# TALLER1.net
KiCad netlist of a schematic drawn in EAGLE
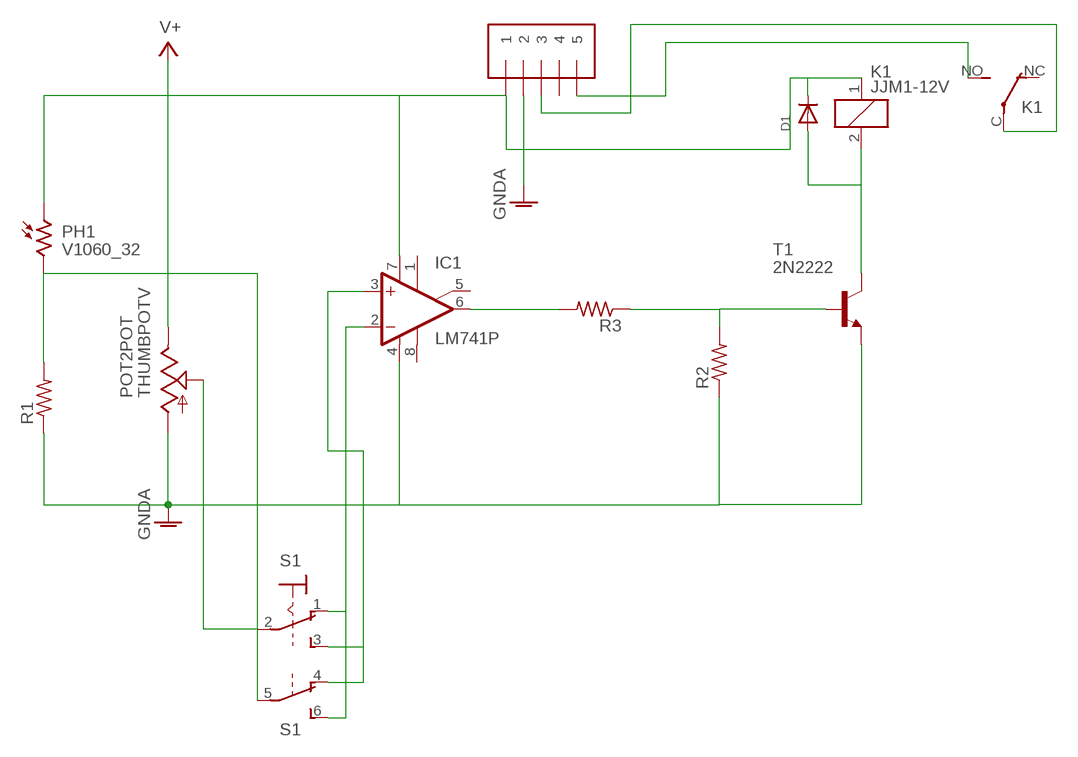
[diagram p0: schematic, sheet 1]

(export (version "E")
  (design (tool "Eeschema 10.0.6"))
  (components
    (comp (ref "D1")
      (value "DIODEDO-1N4148")
      (footprint "eagle-import:DO-1N4148")
      (libsource (lib "eagle-import") (part "DIODEDO-1N4148"))
    )
    (comp (ref "IC1")
      (value "LM741P")
      (footprint "eagle-import:DIL08")
      (libsource (lib "eagle-import") (part "741PLM"))
    )
    (comp (ref "J2")
      (value "1X5")
      (footprint "eagle-import:1X05-3.5MM")
      (libsource (lib "eagle-import") (part "1X5"))
    )
    (comp (ref "K1")
      (value "JJM1-12V")
      (footprint "eagle-import:JJM1C")
      (fields (field (name "MF") "AROMAT/ MATSUSHITA"))
      (libsource (lib "eagle-import") (part "JJM1-12V"))
    )
    (comp (ref "PH1")
      (value "V1060_32")
      (footprint "eagle-import:TO-5_V10")
      (libsource (lib "eagle-import") (part "?1060V_32"))
    )
    (comp (ref "POT2")
      (value "THUMBPOTV")
      (footprint "eagle-import:THUMBWHEELV")
      (libsource (lib "eagle-import") (part "THUMBPOTV"))
    )
    (comp (ref "R1")
      (value "R-US_0207/10")
      (footprint "eagle-import:0207_10")
      (libsource (lib "eagle-import") (part "R-US_0207/10"))
    )
    (comp (ref "R2")
      (value "R-US_0207/10")
      (footprint "eagle-import:0207_10")
      (libsource (lib "eagle-import") (part "R-US_0207/10"))
    )
    (comp (ref "R3")
      (value "R-US_0207/10")
      (footprint "eagle-import:0207_10")
      (libsource (lib "eagle-import") (part "R-US_0207/10"))
    )
    (comp (ref "S1")
      (value "320-938")
      (footprint "eagle-import:320-938")
      (libsource (lib "eagle-import") (part "320-938"))
    )
    (comp (ref "T1")
      (value "2N2222")
      (footprint "eagle-import:TO18")
      (libsource (lib "eagle-import") (part "2N2222"))
    )
  )
  (nets
    (net (code "1") (name "GNDA") (class "Default")
      (node (ref "IC1") (pin "4") (pinfunction "V-_4") (pintype "power_in"))
      (node (ref "J2") (pin "2") (pinfunction "2_2") (pintype "passive"))
      (node (ref "POT2") (pin "A") (pinfunction "A_A") (pintype "passive"))
      (node (ref "R1") (pin "1") (pinfunction "1_1") (pintype "passive"))
      (node (ref "R2") (pin "1") (pinfunction "1_1") (pintype "passive"))
      (node (ref "T1") (pin "1") (pinfunction "E_1") (pintype "passive"))
    )
    (net (code "2") (name "Net-(IC1-+IN)") (class "Default")
      (node (ref "IC1") (pin "3") (pinfunction "+IN_3") (pintype "input"))
      (node (ref "S1") (pin "3") (pinfunction "S_3") (pintype "passive"))
      (node (ref "S1") (pin "4") (pinfunction "O_4") (pintype "passive"))
    )
    (net (code "3") (name "Net-(IC1--IN)") (class "Default")
      (node (ref "IC1") (pin "2") (pinfunction "-IN_2") (pintype "input"))
      (node (ref "S1") (pin "1") (pinfunction "O_1") (pintype "passive"))
      (node (ref "S1") (pin "6") (pinfunction "S_6") (pintype "passive"))
    )
    (net (code "4") (name "Net-(IC1-OUT)") (class "Default")
      (node (ref "IC1") (pin "6") (pinfunction "OUT_6") (pintype "output"))
      (node (ref "R3") (pin "2") (pinfunction "2_2") (pintype "passive"))
    )
    (net (code "5") (name "Net-(K1B-P)") (class "Default")
      (node (ref "J2") (pin "3") (pinfunction "3_3") (pintype "passive"))
      (node (ref "K1") (pin "C") (pinfunction "P_C") (pintype "passive"))
    )
    (net (code "6") (name "Net-(K1B-S)") (class "Default")
      (node (ref "J2") (pin "5") (pinfunction "5_5") (pintype "passive"))
      (node (ref "K1") (pin "NO") (pinfunction "S_NO") (pintype "passive"))
    )
    (net (code "7") (name "Net-(S1A-P)") (class "Default")
      (node (ref "POT2") (pin "S") (pinfunction "S_S") (pintype "passive"))
      (node (ref "S1") (pin "2") (pinfunction "P_2") (pintype "passive"))
    )
    (net (code "8") (name "Net-(S1B-P)") (class "Default")
      (node (ref "PH1") (pin "2") (pinfunction "2_2") (pintype "passive"))
      (node (ref "R1") (pin "2") (pinfunction "2_2") (pintype "passive"))
      (node (ref "S1") (pin "5") (pinfunction "P_5") (pintype "passive"))
    )
    (net (code "9") (name "Net-(T1-B)") (class "Default")
      (node (ref "R2") (pin "2") (pinfunction "2_2") (pintype "passive"))
      (node (ref "R3") (pin "1") (pinfunction "1_1") (pintype "passive"))
      (node (ref "T1") (pin "2") (pinfunction "B_2") (pintype "passive"))
    )
    (net (code "10") (name "Net-(T1-C)") (class "Default")
      (node (ref "D1") (pin "A") (pinfunction "A_A") (pintype "passive"))
      (node (ref "K1") (pin "2") (pinfunction "2_2") (pintype "passive"))
      (node (ref "T1") (pin "3") (pinfunction "C_3") (pintype "passive"))
    )
    (net (code "11") (name "V+") (class "Default")
      (node (ref "D1") (pin "C") (pinfunction "C_C") (pintype "passive"))
      (node (ref "IC1") (pin "7") (pinfunction "V+_7") (pintype "power_in"))
      (node (ref "J2") (pin "1") (pinfunction "1_1") (pintype "passive"))
      (node (ref "K1") (pin "1") (pinfunction "1_1") (pintype "passive"))
      (node (ref "PH1") (pin "1") (pinfunction "1_1") (pintype "passive"))
      (node (ref "POT2") (pin "E") (pinfunction "E_E") (pintype "passive"))
    )
    (net (code "12") (name "unconnected-(IC1-ON1-Pad1)") (class "Default")
      (node (ref "IC1") (pin "1") (pinfunction "ON1_1") (pintype "passive"))
    )
    (net (code "13") (name "unconnected-(IC1-ON2-Pad5)") (class "Default")
      (node (ref "IC1") (pin "5") (pinfunction "ON2_5") (pintype "passive"))
    )
    (net (code "14") (name "unconnected-(IC1-OPT-Pad8)") (class "Default")
      (node (ref "IC1") (pin "8") (pinfunction "OPT_8") (pintype "passive"))
    )
    (net (code "15") (name "unconnected-(J2-Pad4)") (class "Default")
      (node (ref "J2") (pin "4") (pinfunction "4_4") (pintype "passive"))
    )
    (net (code "16") (name "unconnected-(K1B-O-PadNC)") (class "Default")
      (node (ref "K1") (pin "NC") (pinfunction "O_NC") (pintype "passive"))
    )
  )
)
